# MCU099_03_XDS110-ET_EnergyTrace.net
KiCad netlist of a schematic drawn in Altium Designer
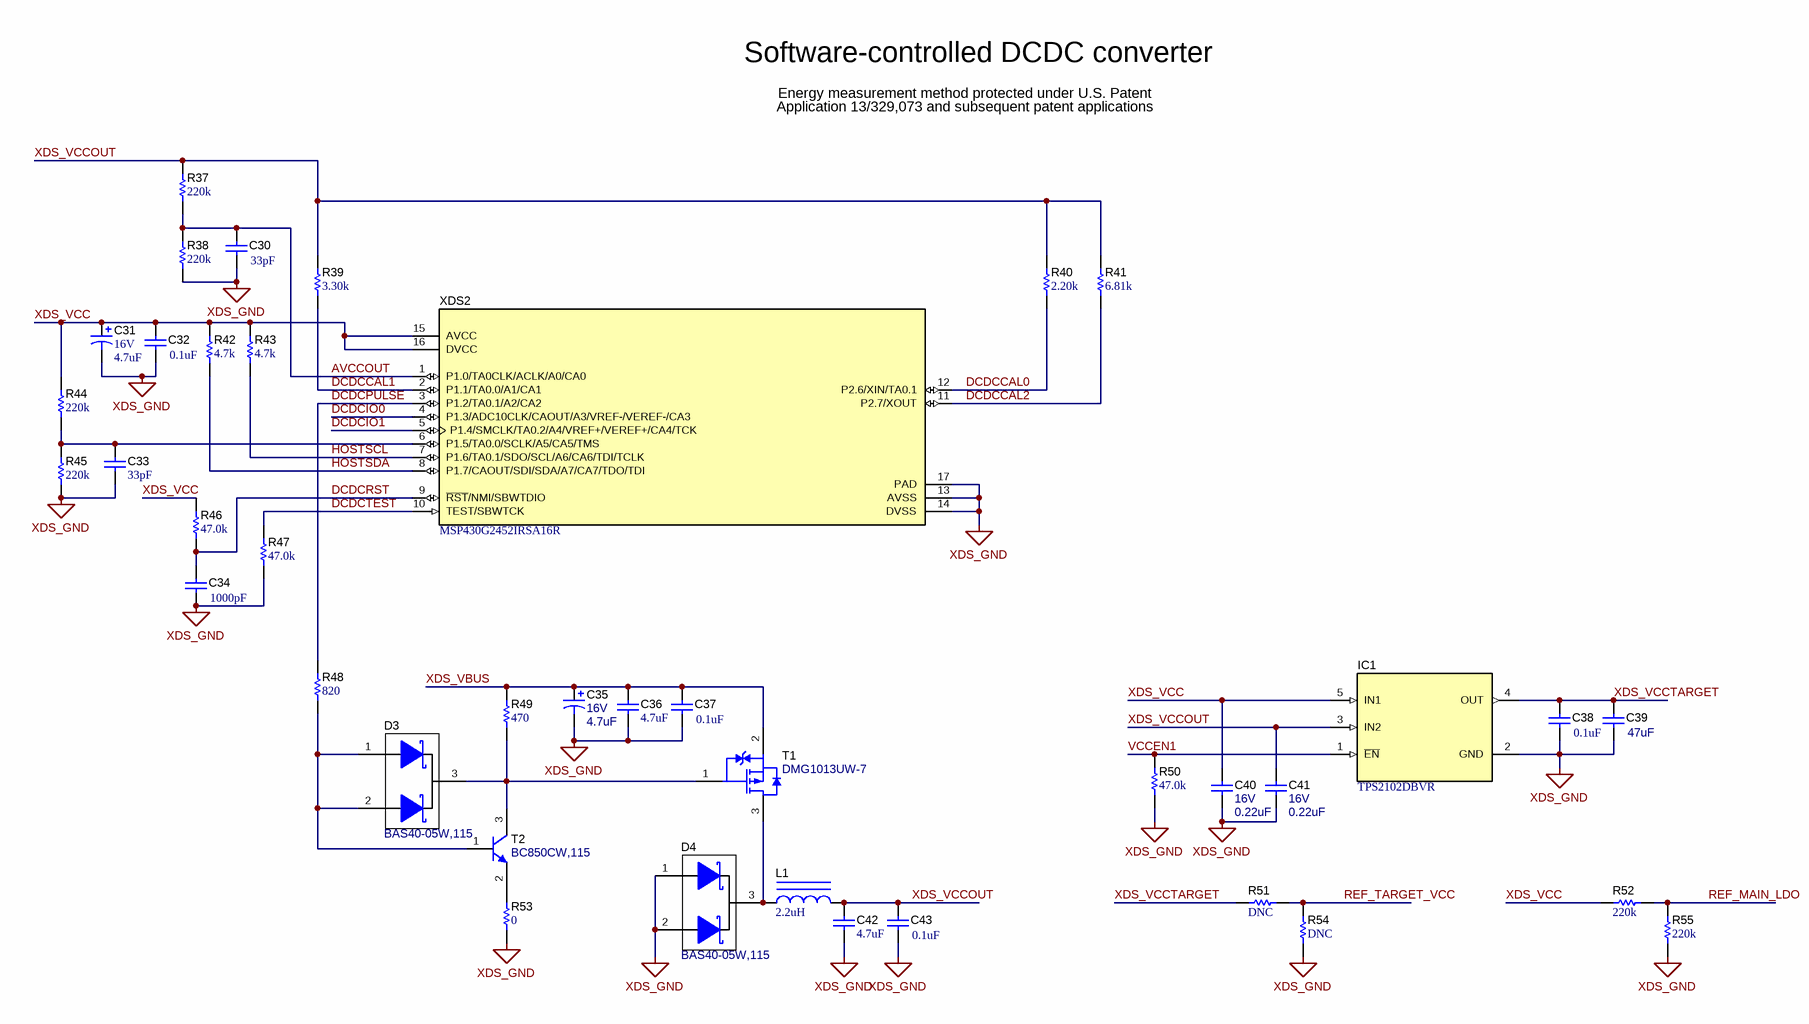
[diagram p0: MCU099_03_XDS110-ET_EnergyTrace.SchDoc]

(export (version "E")
  (design (tool "Eeschema 10.0.6"))
  (components
    (comp (ref "C30")
      (value "GRM1555C1H330JA01D")
      (footprint "0402")
      (description "CAP, CERM, 33 pF, 50 V, +/- 5%, C0G/NP0, 0402")
      (fields
        (field (name "MANUFACTURER") "MuRata")
        (field (name "VALUEDISPLAYED") "33pF")
        (field (name "PUBLISHER") "Texas Instruments")
      )
      (libsource (lib "Altium Vault - TI") (part "Capacitor"))
    )
    (comp (ref "C31")
      (value "TAJA475K016RNJ")
      (footprint "3216-18")
      (description "CAP, TA, 4.7 uF, 16 V, +/- 10%, 4 ohm, SMD")
      (fields
        (field (name "MANUFACTURER") "AVX")
        (field (name "VDC_V") "16V")
        (field (name "VALUEDISPLAYED") "4.7uF")
        (field (name "PUBLISHER") "Texas Instruments")
      )
      (libsource (lib "Altium Vault - TI") (part "Cap_Polarized"))
    )
    (comp (ref "C32")
      (value "C1005X5R1A104K050BA")
      (footprint "0402")
      (description "CAP, CERM, 0.1 uF, 10 V, +/- 10%, X5R, 0402")
      (fields
        (field (name "MANUFACTURER") "TDK")
        (field (name "VALUEDISPLAYED") "0.1uF")
        (field (name "PUBLISHER") "Texas Instruments")
      )
      (libsource (lib "Altium Vault - TI") (part "Capacitor"))
    )
    (comp (ref "C33")
      (value "GRM1555C1H330JA01D")
      (footprint "0402")
      (description "CAP, CERM, 33 pF, 50 V, +/- 5%, C0G/NP0, 0402")
      (fields
        (field (name "MANUFACTURER") "MuRata")
        (field (name "VALUEDISPLAYED") "33pF")
        (field (name "PUBLISHER") "Texas Instruments")
      )
      (libsource (lib "Altium Vault - TI") (part "Capacitor"))
    )
    (comp (ref "C34")
      (value "GRM155R60J102KA01D")
      (footprint "0402")
      (description "CAP, CERM, 1000 pF, 6.3 V, +/- 10%, X5R, 0402")
      (fields
        (field (name "MANUFACTURER") "MuRata")
        (field (name "VALUEDISPLAYED") "1000pF")
        (field (name "PUBLISHER") "Texas Instruments")
      )
      (libsource (lib "Altium Vault - TI") (part "Capacitor"))
    )
    (comp (ref "C35")
      (value "TAJA475K016RNJ")
      (footprint "3216-18")
      (description "CAP, TA, 4.7 uF, 16 V, +/- 10%, 4 ohm, SMD")
      (fields
        (field (name "MANUFACTURER") "AVX")
        (field (name "VDC_V") "16V")
        (field (name "VALUEDISPLAYED") "4.7uF")
        (field (name "PUBLISHER") "Texas Instruments")
      )
      (libsource (lib "Altium Vault - TI") (part "Cap_Polarized"))
    )
    (comp (ref "C36")
      (value "GRM188R61C475KAAJ")
      (footprint "0603")
      (description "CAP, CERM, 4.7 uF, 16 V, +/- 10%, X5R, 0603")
      (fields
        (field (name "MANUFACTURER") "MuRata")
        (field (name "VALUEDISPLAYED") "4.7uF")
        (field (name "PUBLISHER") "Texas Instruments")
      )
      (libsource (lib "Altium Vault - TI") (part "Capacitor"))
    )
    (comp (ref "C37")
      (value "C1005X5R1A104K050BA")
      (footprint "0402")
      (description "CAP, CERM, 0.1 uF, 10 V, +/- 10%, X5R, 0402")
      (fields
        (field (name "MANUFACTURER") "TDK")
        (field (name "VALUEDISPLAYED") "0.1uF")
        (field (name "PUBLISHER") "Texas Instruments")
      )
      (libsource (lib "Altium Vault - TI") (part "Capacitor"))
    )
    (comp (ref "C38")
      (value "C1005X5R1A104K050BA")
      (footprint "0402")
      (description "CAP, CERM, 0.1 uF, 10 V, +/- 10%, X5R, 0402")
      (fields
        (field (name "MANUFACTURER") "TDK")
        (field (name "VALUEDISPLAYED") "0.1uF")
        (field (name "PUBLISHER") "Texas Instruments")
      )
      (libsource (lib "Altium Vault - TI") (part "Capacitor"))
    )
    (comp (ref "C39")
      (value "GRM188R60J476ME15D")
      (footprint "0603")
      (description "CAP, CERM, 47 uF, 6.3 V, +/- 20%, X5R, 0603")
      (fields
        (field (name "MANUFACTURER") "MuRata")
        (field (name "VALUEDISPLAYED") "47uF")
        (field (name "PUBLISHER") "Texas Instruments")
      )
      (libsource (lib "Altium Vault - TI") (part "Capacitor"))
    )
    (comp (ref "C40")
      (value "GRM155R71C224KA12D")
      (footprint "0402")
      (description "CAP, CERM, 0.22 uF, 16 V, +/- 10%, X7R, 0402")
      (fields
        (field (name "MANUFACTURER") "MuRata")
        (field (name "VDC_V") "16V")
        (field (name "VALUEDISPLAYED") "0.22uF")
        (field (name "PUBLISHER") "Texas Instruments")
      )
      (libsource (lib "Altium Vault - TI") (part "Capacitor"))
    )
    (comp (ref "C41")
      (value "GRM155R71C224KA12D")
      (footprint "0402")
      (description "CAP, CERM, 0.22 uF, 16 V, +/- 10%, X7R, 0402")
      (fields
        (field (name "MANUFACTURER") "MuRata")
        (field (name "VDC_V") "16V")
        (field (name "VALUEDISPLAYED") "0.22uF")
        (field (name "PUBLISHER") "Texas Instruments")
      )
      (libsource (lib "Altium Vault - TI") (part "Capacitor"))
    )
    (comp (ref "C42")
      (value "GRM188R61C475KAAJ")
      (footprint "0603")
      (description "CAP, CERM, 4.7 uF, 16 V, +/- 10%, X5R, 0603")
      (fields
        (field (name "MANUFACTURER") "MuRata")
        (field (name "VALUEDISPLAYED") "4.7uF")
        (field (name "PUBLISHER") "Texas Instruments")
      )
      (libsource (lib "Altium Vault - TI") (part "Capacitor"))
    )
    (comp (ref "C43")
      (value "C1005X5R1A104K050BA")
      (footprint "0402")
      (description "CAP, CERM, 0.1 uF, 10 V, +/- 10%, X5R, 0402")
      (fields
        (field (name "MANUFACTURER") "TDK")
        (field (name "VALUEDISPLAYED") "0.1uF")
        (field (name "PUBLISHER") "Texas Instruments")
      )
      (libsource (lib "Altium Vault - TI") (part "Capacitor"))
    )
    (comp (ref "D3")
      (value "BAS40-05W,115")
      (footprint "SOT-323")
      (description "Diode, Schottky, 40 V, 0.12 A, AEC-Q101, SOT-323")
      (fields (field (name "MANUFACTURER") "Nexperia") (field (name "PUBLISHER") "Texas Instruments"))
      (libsource (lib "Altium Vault - TI") (part "DIODE_SCHOTTKY_A1C3_A2C3"))
    )
    (comp (ref "D4")
      (value "BAS40-05W,115")
      (footprint "SOT-323")
      (description "Diode, Schottky, 40 V, 0.12 A, AEC-Q101, SOT-323")
      (fields (field (name "MANUFACTURER") "Nexperia") (field (name "PUBLISHER") "Texas Instruments"))
      (libsource (lib "Altium Vault - TI") (part "DIODE_SCHOTTKY_A1C3_A2C3"))
    )
    (comp (ref "IC1")
      (value "TPS2102DBVR")
      (footprint "DBV0005A_N")
      (fields
        (field (name "ALTERNATE PARTNUMBER") "TPS2102DBVT")
        (field (name "MANUFACTURER") "Texas Instruments")
        (field (name "PARTNUMBER") "TPS2102DBVR")
        (field (name "PUBLISHER") "Texas Instruments")
      )
      (libsource (lib "Altium Vault - TI") (part "TPS2102DBV"))
    )
    (comp (ref "L1")
      (value "CBC2518T2R2M")
      (footprint "CBC2518")
      (description "Inductor, Wirewound, Ceramic, 2.2 uH, 0.89 A, 0.13 ohm, SMD")
      (fields
        (field (name "MANUFACTURER") "Taiyo Yuden")
        (field (name "VALUEDISPLAYED") "2.2uH")
        (field (name "PUBLISHER") "Texas Instruments")
      )
      (libsource (lib "Altium Vault - TI") (part "Inductor_Iron"))
    )
    (comp (ref "R37")
      (value "RC0402FR-07220KL")
      (footprint "0402")
      (description "RES, 220 k, 1%, 0.0625 W, 0402")
      (fields
        (field (name "MANUFACTURER") "Yageo America")
        (field (name "VALUEDISPLAYED") "220k")
        (field (name "PUBLISHER") "Texas Instruments")
      )
      (libsource (lib "Altium Vault - TI") (part "Resistor"))
    )
    (comp (ref "R38")
      (value "RC0402FR-07220KL")
      (footprint "0402")
      (description "RES, 220 k, 1%, 0.0625 W, 0402")
      (fields
        (field (name "MANUFACTURER") "Yageo America")
        (field (name "VALUEDISPLAYED") "220k")
        (field (name "PUBLISHER") "Texas Instruments")
      )
      (libsource (lib "Altium Vault - TI") (part "Resistor"))
    )
    (comp (ref "R39")
      (value "ERJ-2RKF3301X")
      (footprint "0402")
      (description "RES, 3.30 k, 1%, 0.1 W, AEC-Q200 Grade 0, 0402")
      (fields
        (field (name "MANUFACTURER") "Panasonic")
        (field (name "VALUEDISPLAYED") "3.30k")
        (field (name "PUBLISHER") "Texas Instruments")
      )
      (libsource (lib "Altium Vault - TI") (part "Resistor"))
    )
    (comp (ref "R40")
      (value "CRCW04022K20FKED")
      (footprint "0402")
      (description "RES, 2.20 k, 1%, 0.063 W, 0402")
      (fields
        (field (name "MANUFACTURER") "Vishay-Dale")
        (field (name "VALUEDISPLAYED") "2.20k")
        (field (name "PUBLISHER") "Texas Instruments")
      )
      (libsource (lib "Altium Vault - TI") (part "Resistor"))
    )
    (comp (ref "R41")
      (value "CRCW04026K81FKED")
      (footprint "0402")
      (description "RES, 6.81 k, 1%, 0.063 W, 0402")
      (fields
        (field (name "MANUFACTURER") "Vishay-Dale")
        (field (name "VALUEDISPLAYED") "6.81k")
        (field (name "PUBLISHER") "Texas Instruments")
      )
      (libsource (lib "Altium Vault - TI") (part "Resistor"))
    )
    (comp (ref "R42")
      (value "CRCW04024K70JNED")
      (footprint "0402")
      (description "RES, 4.7 k, 5%, 0.063 W, 0402")
      (fields
        (field (name "MANUFACTURER") "Vishay-Dale")
        (field (name "VALUEDISPLAYED") "4.7k")
        (field (name "PUBLISHER") "Texas Instruments")
      )
      (libsource (lib "Altium Vault - TI") (part "Resistor"))
    )
    (comp (ref "R43")
      (value "CRCW04024K70JNED")
      (footprint "0402")
      (description "RES, 4.7 k, 5%, 0.063 W, 0402")
      (fields
        (field (name "MANUFACTURER") "Vishay-Dale")
        (field (name "VALUEDISPLAYED") "4.7k")
        (field (name "PUBLISHER") "Texas Instruments")
      )
      (libsource (lib "Altium Vault - TI") (part "Resistor"))
    )
    (comp (ref "R44")
      (value "RC0402FR-07220KL")
      (footprint "0402")
      (description "RES, 220 k, 1%, 0.0625 W, 0402")
      (fields
        (field (name "MANUFACTURER") "Yageo America")
        (field (name "VALUEDISPLAYED") "220k")
        (field (name "PUBLISHER") "Texas Instruments")
      )
      (libsource (lib "Altium Vault - TI") (part "Resistor"))
    )
    (comp (ref "R45")
      (value "RC0402FR-07220KL")
      (footprint "0402")
      (description "RES, 220 k, 1%, 0.0625 W, 0402")
      (fields
        (field (name "MANUFACTURER") "Yageo America")
        (field (name "VALUEDISPLAYED") "220k")
        (field (name "PUBLISHER") "Texas Instruments")
      )
      (libsource (lib "Altium Vault - TI") (part "Resistor"))
    )
    (comp (ref "R46")
      (value "RC0402FR-0747KL")
      (footprint "0402")
      (description "RES, 47.0 k, 1%, 0.0625 W, 0402")
      (fields
        (field (name "MANUFACTURER") "Yageo America")
        (field (name "VALUEDISPLAYED") "47.0k")
        (field (name "PUBLISHER") "Texas Instruments")
      )
      (libsource (lib "Altium Vault - TI") (part "Resistor"))
    )
    (comp (ref "R47")
      (value "RC0402FR-0747KL")
      (footprint "0402")
      (description "RES, 47.0 k, 1%, 0.0625 W, 0402")
      (fields
        (field (name "MANUFACTURER") "Yageo America")
        (field (name "VALUEDISPLAYED") "47.0k")
        (field (name "PUBLISHER") "Texas Instruments")
      )
      (libsource (lib "Altium Vault - TI") (part "Resistor"))
    )
    (comp (ref "R48")
      (value "RC0402FR-07820RL")
      (footprint "0402")
      (description "RES, 820, 1%, 0.063 W, 0402")
      (fields
        (field (name "MANUFACTURER") "Yageo America")
        (field (name "VALUEDISPLAYED") "820")
        (field (name "PUBLISHER") "Texas Instruments")
      )
      (libsource (lib "Altium Vault - TI") (part "Resistor"))
    )
    (comp (ref "R49")
      (value "CRCW0402470RJNED")
      (footprint "0402")
      (description "RES, 470, 5%, 0.063 W, 0402")
      (fields
        (field (name "MANUFACTURER") "Vishay-Dale")
        (field (name "VALUEDISPLAYED") "470")
        (field (name "PUBLISHER") "Texas Instruments")
      )
      (libsource (lib "Altium Vault - TI") (part "Resistor"))
    )
    (comp (ref "R50")
      (value "RC0402FR-0747KL")
      (footprint "0402")
      (description "RES, 47.0 k, 1%, 0.0625 W, 0402")
      (fields
        (field (name "MANUFACTURER") "Yageo America")
        (field (name "VALUEDISPLAYED") "47.0k")
        (field (name "PUBLISHER") "Texas Instruments")
      )
      (libsource (lib "Altium Vault - TI") (part "Resistor"))
    )
    (comp (ref "R51")
      (value "CRCW04024K70JNED")
      (footprint "0402")
      (description "RES, 4.7 k, 5%, 0.063 W, 0402")
      (fields
        (field (name "MANUFACTURER") "Vishay-Dale")
        (field (name "VALUEDISPLAYED") "DNC")
        (field (name "PUBLISHER") "Texas Instruments")
      )
      (libsource (lib "Altium Vault - TI") (part "Resistor"))
    )
    (comp (ref "R52")
      (value "CRCW0402220KJNED")
      (footprint "0402")
      (description "RES, 220 k, 5%, 0.063 W, AEC-Q200 Grade 0, 0402")
      (fields (field (name "MANUFACTURER") "Vishay-Dale") (field (name "VALUEDISPLAYED") "220k"))
      (libsource (lib "Altium Vault - TI") (part "Resistor"))
    )
    (comp (ref "R53")
      (value "RC0603JR-070RL")
      (footprint "0603")
      (description "RES, 0, 5%, 0.1 W, 0603")
      (fields (field (name "MANUFACTURER") "Yageo") (field (name "VALUEDISPLAYED") "0"))
      (libsource (lib "Altium Vault - TI") (part "Resistor"))
    )
    (comp (ref "R54")
      (value "CRCW04024K70JNED")
      (footprint "0402")
      (description "RES, 4.7 k, 5%, 0.063 W, 0402")
      (fields
        (field (name "MANUFACTURER") "Vishay-Dale")
        (field (name "VALUEDISPLAYED") "DNC")
        (field (name "PUBLISHER") "Texas Instruments")
      )
      (libsource (lib "Altium Vault - TI") (part "Resistor"))
    )
    (comp (ref "R55")
      (value "CRCW0402220KJNED")
      (footprint "0402")
      (description "RES, 220 k, 5%, 0.063 W, AEC-Q200 Grade 0, 0402")
      (fields (field (name "MANUFACTURER") "Vishay-Dale") (field (name "VALUEDISPLAYED") "220k"))
      (libsource (lib "Altium Vault - TI") (part "Resistor"))
    )
    (comp (ref "T1")
      (value "DMG1013UW-7")
      (footprint "SOT-323")
      (description "MOSFET, P-CH, -20 V, -0.82 A, SOT-323")
      (fields (field (name "MANUFACTURER") "Diodes Inc.") (field (name "PUBLISHER") "Texas Instruments"))
      (libsource (lib "Altium Vault - TI") (part "MOSFET_P_D3G1S2_PD"))
    )
    (comp (ref "T2")
      (value "BC850CW,115")
      (footprint "SOT-323")
      (description "Transistor, NPN, 45 V, 0.1 A, SOT-323")
      (fields
        (field (name "MANUFACTURER") "NXP Semiconductor")
        (field (name "PUBLISHER") "Texas Instruments")
      )
      (libsource (lib "Altium Vault - TI") (part "BJT_NPN_C3B1E2"))
    )
    (comp (ref "XDS2")
      (value "MSP430G2452IRSA16R")
      (footprint "RSA0016B")
      (description "MSP430G2x52, MSP430G2x12 Mixed Signal Microcontroller, RSA0016B (VQFN-16)")
      (fields
        (field (name "PARTNUMBER") "MSP430G2452IRSA16R")
        (field (name "MANUFACTURER") "Texas Instruments")
        (field (name "ALTERNATE PARTNUMBER") "MSP430G2452IRSA16T")
      )
      (libsource (lib "Altium Vault - TI") (part "MSP430G2452IRSA"))
    )
  )
  (nets
    (net (code "1") (name "/AVCCOUT") (class "Default")
      (node (ref "C30") (pin "1") (pinfunction "1_1") (pintype "passive"))
      (node (ref "R37") (pin "1") (pinfunction "1_1") (pintype "passive"))
      (node (ref "R38") (pin "2") (pinfunction "2_2") (pintype "passive"))
      (node (ref "XDS2") (pin "1") (pinfunction "P1.0/TA0CLK/ACLK/A0/CA0_1") (pintype "bidirectional"))
    )
    (net (code "2") (name "/DCDCCAL0") (class "Default")
      (node (ref "R40") (pin "1") (pinfunction "1_1") (pintype "passive"))
      (node (ref "XDS2") (pin "12") (pinfunction "P2.6/XIN/TA0.1_12") (pintype "bidirectional"))
    )
    (net (code "3") (name "/DCDCCAL1") (class "Default")
      (node (ref "R39") (pin "1") (pinfunction "1_1") (pintype "passive"))
      (node (ref "XDS2") (pin "2") (pinfunction "P1.1/TA0.0/A1/CA1_2") (pintype "bidirectional"))
    )
    (net (code "4") (name "/DCDCCAL2") (class "Default")
      (node (ref "R41") (pin "1") (pinfunction "1_1") (pintype "passive"))
      (node (ref "XDS2") (pin "11") (pinfunction "P2.7/XOUT_11") (pintype "bidirectional"))
    )
    (net (code "5") (name "/DCDCIO0") (class "Default")
      (node (ref "XDS2") (pin "4") (pinfunction "P1.3/ADC10CLK/CAOUT/A3/VREF-/VEREF-/CA3_4") (pintype "bidirectional"))
    )
    (net (code "6") (name "/DCDCIO1") (class "Default")
      (node (ref "XDS2") (pin "5") (pinfunction "P1.4/SMCLK/TA0.2/A4/VREF+/VEREF+/CA4/TCK_5") (pintype "bidirectional"))
    )
    (net (code "7") (name "/DCDCPULSE") (class "Default")
      (node (ref "R48") (pin "2") (pinfunction "2_2") (pintype "passive"))
      (node (ref "XDS2") (pin "3") (pinfunction "P1.2/TA0.1/A2/CA2_3") (pintype "bidirectional"))
    )
    (net (code "8") (name "/DCDCRST") (class "Default")
      (node (ref "C34") (pin "1") (pinfunction "1_1") (pintype "passive"))
      (node (ref "R46") (pin "1") (pinfunction "1_1") (pintype "passive"))
      (node (ref "XDS2") (pin "9") (pinfunction "~{RST}/NMI/SBWTDIO_9") (pintype "bidirectional"))
    )
    (net (code "9") (name "/DCDCTEST") (class "Default")
      (node (ref "R47") (pin "2") (pinfunction "2_2") (pintype "passive"))
      (node (ref "XDS2") (pin "10") (pinfunction "TEST/SBWTCK_10") (pintype "input"))
    )
    (net (code "10") (name "/HOSTSCL") (class "Default")
      (node (ref "R43") (pin "1") (pinfunction "1_1") (pintype "passive"))
      (node (ref "XDS2") (pin "7") (pinfunction "P1.6/TA0.1/SDO/SCL/A6/CA6/TDI/TCLK_7") (pintype "bidirectional"))
    )
    (net (code "11") (name "/HOSTSDA") (class "Default")
      (node (ref "R42") (pin "1") (pinfunction "1_1") (pintype "passive"))
      (node (ref "XDS2") (pin "8") (pinfunction "P1.7/CAOUT/SDI/SDA/A7/CA7/TDO/TDI_8") (pintype "bidirectional"))
    )
    (net (code "12") (name "/REF_MAIN_LDO") (class "Default")
      (node (ref "R52") (pin "1") (pinfunction "1_1") (pintype "passive"))
      (node (ref "R55") (pin "2") (pinfunction "2_2") (pintype "passive"))
    )
    (net (code "13") (name "/REF_TARGET_VCC") (class "Default")
      (node (ref "R51") (pin "1") (pinfunction "1_1") (pintype "passive"))
      (node (ref "R54") (pin "2") (pinfunction "2_2") (pintype "passive"))
    )
    (net (code "14") (name "/VCCEN1") (class "Default")
      (node (ref "IC1") (pin "1") (pinfunction "EN_1") (pintype "input"))
      (node (ref "R50") (pin "2") (pinfunction "2_2") (pintype "passive"))
    )
    (net (code "15") (name "/XDS_VBUS") (class "Default")
      (node (ref "C35") (pin "1") (pinfunction "+_1") (pintype "passive"))
      (node (ref "C36") (pin "2") (pinfunction "2_2") (pintype "passive"))
      (node (ref "C37") (pin "1") (pinfunction "1_1") (pintype "passive"))
      (node (ref "R49") (pin "2") (pinfunction "2_2") (pintype "passive"))
      (node (ref "T1") (pin "2") (pinfunction "S_2") (pintype "passive"))
    )
    (net (code "16") (name "/XDS_VCC") (class "Default")
      (node (ref "C31") (pin "1") (pinfunction "+_1") (pintype "passive"))
      (node (ref "C32") (pin "1") (pinfunction "1_1") (pintype "passive"))
      (node (ref "C40") (pin "1") (pinfunction "1_1") (pintype "passive"))
      (node (ref "IC1") (pin "5") (pinfunction "IN1_5") (pintype "input"))
      (node (ref "R42") (pin "2") (pinfunction "2_2") (pintype "passive"))
      (node (ref "R43") (pin "2") (pinfunction "2_2") (pintype "passive"))
      (node (ref "R44") (pin "2") (pinfunction "2_2") (pintype "passive"))
      (node (ref "R46") (pin "2") (pinfunction "2_2") (pintype "passive"))
      (node (ref "R52") (pin "2") (pinfunction "2_2") (pintype "passive"))
      (node (ref "XDS2") (pin "15") (pinfunction "AVCC_15") (pintype "power_in"))
      (node (ref "XDS2") (pin "16") (pinfunction "DVCC_16") (pintype "power_in"))
    )
    (net (code "17") (name "/XDS_VCCOUT") (class "Default")
      (node (ref "C41") (pin "1") (pinfunction "1_1") (pintype "passive"))
      (node (ref "C42") (pin "2") (pinfunction "2_2") (pintype "passive"))
      (node (ref "C43") (pin "1") (pinfunction "1_1") (pintype "passive"))
      (node (ref "IC1") (pin "3") (pinfunction "IN2_3") (pintype "input"))
      (node (ref "L1") (pin "2") (pinfunction "2_2") (pintype "passive"))
      (node (ref "R37") (pin "2") (pinfunction "2_2") (pintype "passive"))
      (node (ref "R39") (pin "2") (pinfunction "2_2") (pintype "passive"))
      (node (ref "R40") (pin "2") (pinfunction "2_2") (pintype "passive"))
      (node (ref "R41") (pin "2") (pinfunction "2_2") (pintype "passive"))
    )
    (net (code "18") (name "/XDS_VCCTARGET") (class "Default")
      (node (ref "C38") (pin "1") (pinfunction "1_1") (pintype "passive"))
      (node (ref "C39") (pin "1") (pinfunction "1_1") (pintype "passive"))
      (node (ref "IC1") (pin "4") (pinfunction "OUT_4") (pintype "output"))
      (node (ref "R51") (pin "2") (pinfunction "2_2") (pintype "passive"))
    )
    (net (code "19") (name "Net-(D3-K)") (class "Default")
      (node (ref "D3") (pin "3") (pinfunction "K_3") (pintype "passive"))
      (node (ref "R49") (pin "1") (pinfunction "1_1") (pintype "passive"))
      (node (ref "T1") (pin "1") (pinfunction "G_1") (pintype "passive"))
      (node (ref "T2") (pin "3") (pinfunction "C_3") (pintype "passive"))
    )
    (net (code "20") (name "Net-(D4-K)") (class "Default")
      (node (ref "D4") (pin "3") (pinfunction "K_3") (pintype "passive"))
      (node (ref "L1") (pin "1") (pinfunction "1_1") (pintype "passive"))
      (node (ref "T1") (pin "3") (pinfunction "D_3") (pintype "passive"))
    )
    (net (code "21") (name "Net-(T2-B)") (class "Default")
      (node (ref "D3") (pin "1") (pinfunction "A_1") (pintype "passive"))
      (node (ref "D3") (pin "2") (pinfunction "A_2") (pintype "passive"))
      (node (ref "R48") (pin "1") (pinfunction "1_1") (pintype "passive"))
      (node (ref "T2") (pin "1") (pinfunction "B_1") (pintype "passive"))
    )
    (net (code "22") (name "Net-(T2-E)") (class "Default")
      (node (ref "R53") (pin "2") (pinfunction "2_2") (pintype "passive"))
      (node (ref "T2") (pin "2") (pinfunction "E_2") (pintype "passive"))
    )
    (net (code "23") (name "Net-(XDS2-P1.5{slash}TA0.0{slash}SCLK{slash}A5{slash}CA5{slash}TMS)") (class "Default")
      (node (ref "C33") (pin "1") (pinfunction "1_1") (pintype "passive"))
      (node (ref "R44") (pin "1") (pinfunction "1_1") (pintype "passive"))
      (node (ref "R45") (pin "2") (pinfunction "2_2") (pintype "passive"))
      (node (ref "XDS2") (pin "6") (pinfunction "P1.5/TA0.0/SCLK/A5/CA5/TMS_6") (pintype "bidirectional"))
    )
    (net (code "24") (name "XDS_GND") (class "Default")
      (node (ref "C30") (pin "2") (pinfunction "2_2") (pintype "passive"))
      (node (ref "C31") (pin "2") (pinfunction "-_2") (pintype "passive"))
      (node (ref "C32") (pin "2") (pinfunction "2_2") (pintype "passive"))
      (node (ref "C33") (pin "2") (pinfunction "2_2") (pintype "passive"))
      (node (ref "C34") (pin "2") (pinfunction "2_2") (pintype "passive"))
      (node (ref "C35") (pin "2") (pinfunction "-_2") (pintype "passive"))
      (node (ref "C36") (pin "1") (pinfunction "1_1") (pintype "passive"))
      (node (ref "C37") (pin "2") (pinfunction "2_2") (pintype "passive"))
      (node (ref "C38") (pin "2") (pinfunction "2_2") (pintype "passive"))
      (node (ref "C39") (pin "2") (pinfunction "2_2") (pintype "passive"))
      (node (ref "C40") (pin "2") (pinfunction "2_2") (pintype "passive"))
      (node (ref "C41") (pin "2") (pinfunction "2_2") (pintype "passive"))
      (node (ref "C42") (pin "1") (pinfunction "1_1") (pintype "passive"))
      (node (ref "C43") (pin "2") (pinfunction "2_2") (pintype "passive"))
      (node (ref "D4") (pin "1") (pinfunction "A_1") (pintype "passive"))
      (node (ref "D4") (pin "2") (pinfunction "A_2") (pintype "passive"))
      (node (ref "IC1") (pin "2") (pinfunction "GND_2") (pintype "power_in"))
      (node (ref "R38") (pin "1") (pinfunction "1_1") (pintype "passive"))
      (node (ref "R45") (pin "1") (pinfunction "1_1") (pintype "passive"))
      (node (ref "R47") (pin "1") (pinfunction "1_1") (pintype "passive"))
      (node (ref "R50") (pin "1") (pinfunction "1_1") (pintype "passive"))
      (node (ref "R53") (pin "1") (pinfunction "1_1") (pintype "passive"))
      (node (ref "R54") (pin "1") (pinfunction "1_1") (pintype "passive"))
      (node (ref "R55") (pin "1") (pinfunction "1_1") (pintype "passive"))
      (node (ref "XDS2") (pin "13") (pinfunction "AVSS_13") (pintype "power_in"))
      (node (ref "XDS2") (pin "14") (pinfunction "DVSS_14") (pintype "power_in"))
      (node (ref "XDS2") (pin "17") (pinfunction "PAD_17") (pintype "power_in"))
    )
  )
)
